# SerialLvlConvert.net
KiCad netlist of a schematic drawn in Altium Designer
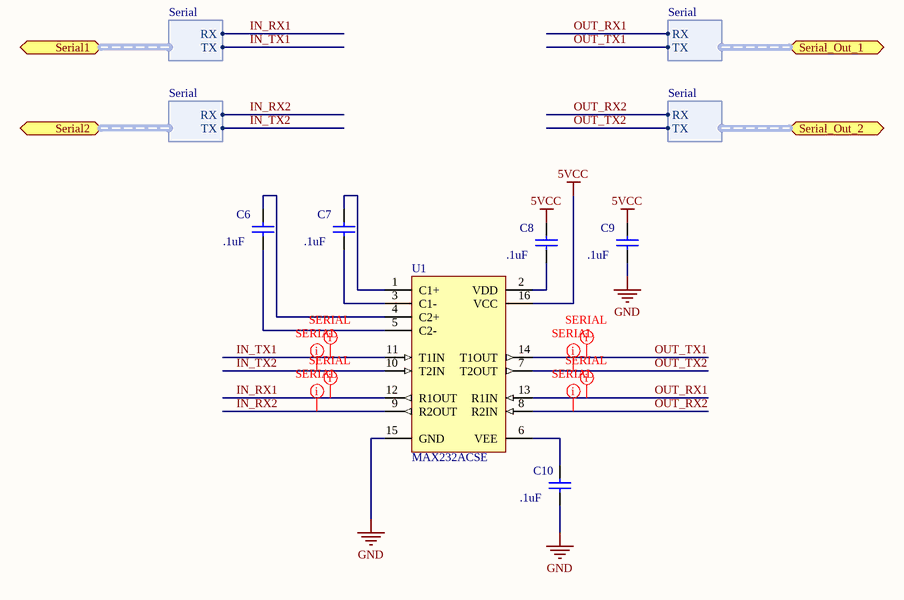
[diagram p0: SerialLvlConvert.SchDoc]

(export (version "E")
  (design (tool "Eeschema 10.0.6"))
  (components
    (comp (ref "C6")
      (value ".1uF")
      (footprint "0402")
      (description "Capacitor (Semiconductor SIM Model)")
      (fields (field (name "Comment") "Cap Semi") (field (name "PUBLISHER") "Altium Limited"))
      (libsource (lib "Miscellaneous Devices") (part "Cap Semi"))
    )
    (comp (ref "C7")
      (value ".1uF")
      (footprint "0402")
      (description "Capacitor (Semiconductor SIM Model)")
      (fields (field (name "Comment") "Cap Semi") (field (name "PUBLISHER") "Altium Limited"))
      (libsource (lib "Miscellaneous Devices") (part "Cap Semi"))
    )
    (comp (ref "C8")
      (value ".1uF")
      (footprint "0402")
      (description "Capacitor (Semiconductor SIM Model)")
      (fields (field (name "Comment") "Cap Semi") (field (name "PUBLISHER") "Altium Limited"))
      (libsource (lib "Miscellaneous Devices") (part "Cap Semi"))
    )
    (comp (ref "C9")
      (value ".1uF")
      (footprint "0402")
      (description "Capacitor (Semiconductor SIM Model)")
      (fields (field (name "Comment") "Cap Semi") (field (name "PUBLISHER") "Altium Limited"))
      (libsource (lib "Miscellaneous Devices") (part "Cap Semi"))
    )
    (comp (ref "C10")
      (value ".1uF")
      (footprint "0402")
      (description "Capacitor (Semiconductor SIM Model)")
      (fields (field (name "Comment") "Cap Semi") (field (name "PUBLISHER") "Altium Limited"))
      (libsource (lib "Miscellaneous Devices") (part "Cap Semi"))
    )
    (comp (ref "U1")
      (value "MAX232ACSE")
      (footprint "Maxim Communication Transceiver:NSO16_N")
      (description "+5V Powered, Multi-Channel RS-232 Driver/Receiver")
      (fields (field (name "PUBLISHER") "Altium Limited"))
      (libsource (lib "Maxim Communication Transceiver") (part "MAX232ACSE"))
    )
  )
  (nets
    (net (code "2") (name "/IN_RX1") (class "Default")
      (node (ref "U1") (pin "12") (pinfunction "R1OUT_12") (pintype "output"))
    )
    (net (code "3") (name "/IN_RX2") (class "Default")
      (node (ref "U1") (pin "9") (pinfunction "R2OUT_9") (pintype "output"))
    )
    (net (code "4") (name "/IN_TX1") (class "Default")
      (node (ref "U1") (pin "11") (pinfunction "T1IN_11") (pintype "input"))
    )
    (net (code "5") (name "/IN_TX2") (class "Default")
      (node (ref "U1") (pin "10") (pinfunction "T2IN_10") (pintype "input"))
    )
    (net (code "6") (name "/OUT_RX1") (class "Default")
      (node (ref "U1") (pin "13") (pinfunction "R1IN_13") (pintype "input"))
    )
    (net (code "7") (name "/OUT_RX2") (class "Default")
      (node (ref "U1") (pin "8") (pinfunction "R2IN_8") (pintype "input"))
    )
    (net (code "8") (name "/OUT_TX1") (class "Default")
      (node (ref "U1") (pin "14") (pinfunction "T1OUT_14") (pintype "output"))
    )
    (net (code "9") (name "/OUT_TX2") (class "Default")
      (node (ref "U1") (pin "7") (pinfunction "T2OUT_7") (pintype "output"))
    )
    (net (code "11") (name "5VCC") (class "Default")
      (node (ref "C8") (pin "1") (pinfunction "1_1") (pintype "passive"))
      (node (ref "C9") (pin "1") (pinfunction "1_1") (pintype "passive"))
      (node (ref "U1") (pin "16") (pinfunction "VCC_16") (pintype "power_in"))
    )
    (net (code "12") (name "GND") (class "Default")
      (node (ref "C10") (pin "2") (pinfunction "2_2") (pintype "passive"))
      (node (ref "C9") (pin "2") (pinfunction "2_2") (pintype "passive"))
      (node (ref "U1") (pin "15") (pinfunction "GND_15") (pintype "power_in"))
    )
    (net (code "13") (name "Net-(U1-C1+)") (class "Default")
      (node (ref "C7") (pin "1") (pinfunction "1_1") (pintype "passive"))
      (node (ref "U1") (pin "1") (pinfunction "C1+_1") (pintype "passive"))
    )
    (net (code "14") (name "Net-(U1-C1-)") (class "Default")
      (node (ref "C7") (pin "2") (pinfunction "2_2") (pintype "passive"))
      (node (ref "U1") (pin "3") (pinfunction "C1-_3") (pintype "passive"))
    )
    (net (code "15") (name "Net-(U1-C2+)") (class "Default")
      (node (ref "C6") (pin "1") (pinfunction "1_1") (pintype "passive"))
      (node (ref "U1") (pin "4") (pinfunction "C2+_4") (pintype "passive"))
    )
    (net (code "16") (name "Net-(U1-C2-)") (class "Default")
      (node (ref "C6") (pin "2") (pinfunction "2_2") (pintype "passive"))
      (node (ref "U1") (pin "5") (pinfunction "C2-_5") (pintype "passive"))
    )
    (net (code "17") (name "Net-(U1-VDD)") (class "Default")
      (node (ref "C8") (pin "2") (pinfunction "2_2") (pintype "passive"))
      (node (ref "U1") (pin "2") (pinfunction "VDD_2") (pintype "power_in"))
    )
    (net (code "18") (name "Net-(U1-VEE)") (class "Default")
      (node (ref "C10") (pin "1") (pinfunction "1_1") (pintype "passive"))
      (node (ref "U1") (pin "6") (pinfunction "VEE_6") (pintype "power_in"))
    )
  )
)
